# LSE_Oscilator.net
KiCad netlist of a schematic drawn in Altium Designer
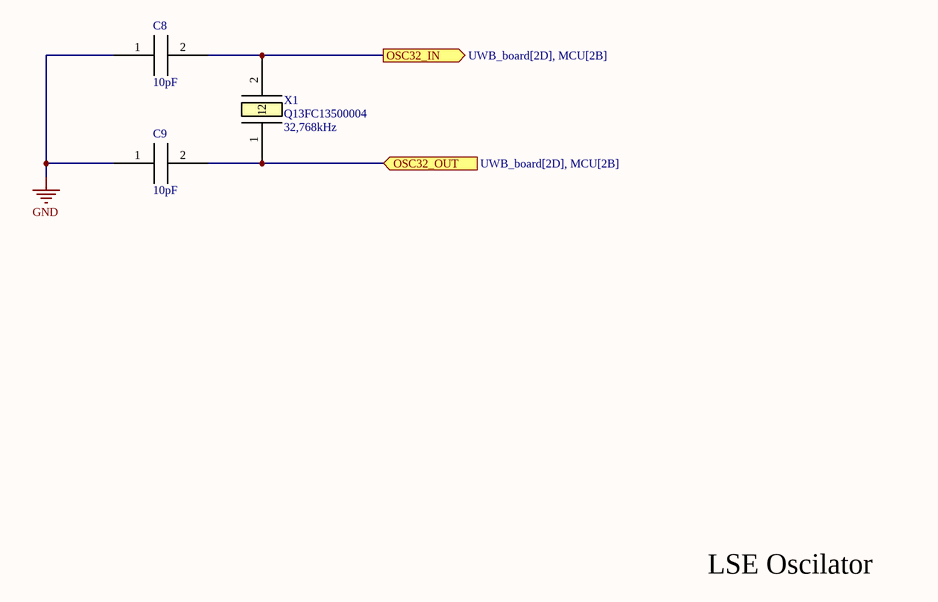
[diagram p0: LSE_Oscilator.SchDoc]

(export (version "E")
  (design (tool "Eeschema 10.0.6"))
  (components
    (comp (ref "C8")
      (value "10pF")
      (footprint "0603_cap")
      (description "10pF 50V C0G ±5% 0603 Multilayer Ceramic Capacitors MLCC - SMD/SMT ROHS")
      (fields (field (name "LCSC PART #") "C1634"))
      (libsource (lib "Schlib1") (part "CL10C100JB8NNNC"))
    )
    (comp (ref "C9")
      (value "10pF")
      (footprint "0603_cap")
      (description "10pF 50V C0G ±5% 0603 Multilayer Ceramic Capacitors MLCC - SMD/SMT ROHS")
      (fields (field (name "LCSC PART #") "C1634"))
      (libsource (lib "Schlib1") (part "CL10C100JB8NNNC"))
    )
    (comp (ref "X1")
      (value "Q13FC13500004")
      (footprint "SMD3215-2P")
      (description "-40℃~+85℃ 12.5pF 32.768kHz 70kΩ Crystal Oscillator ±20ppm SMD3215-2P Crystals ROHS")
      (fields (field (name "LCSC PART #") "C32346") (field (name "PARAMETER") "32,768kHz"))
      (libsource (lib "Schlib1") (part "Q13FC13500004"))
    )
  )
  (nets
    (net (code "1") (name "/OSC32_IN") (class "Default")
      (node (ref "C8") (pin "2") (pinfunction "3_2") (pintype "passive"))
      (node (ref "X1") (pin "2") (pinfunction "2_2") (pintype "passive"))
    )
    (net (code "2") (name "/OSC32_OUT") (class "Default")
      (node (ref "C9") (pin "2") (pinfunction "3_2") (pintype "passive"))
      (node (ref "X1") (pin "1") (pinfunction "1_1") (pintype "passive"))
    )
    (net (code "3") (name "GND") (class "Default")
      (node (ref "C8") (pin "1") (pintype "passive"))
      (node (ref "C9") (pin "1") (pintype "passive"))
    )
  )
)
